# Qwiic-OpenLog.net
KiCad netlist of a schematic drawn in EAGLE
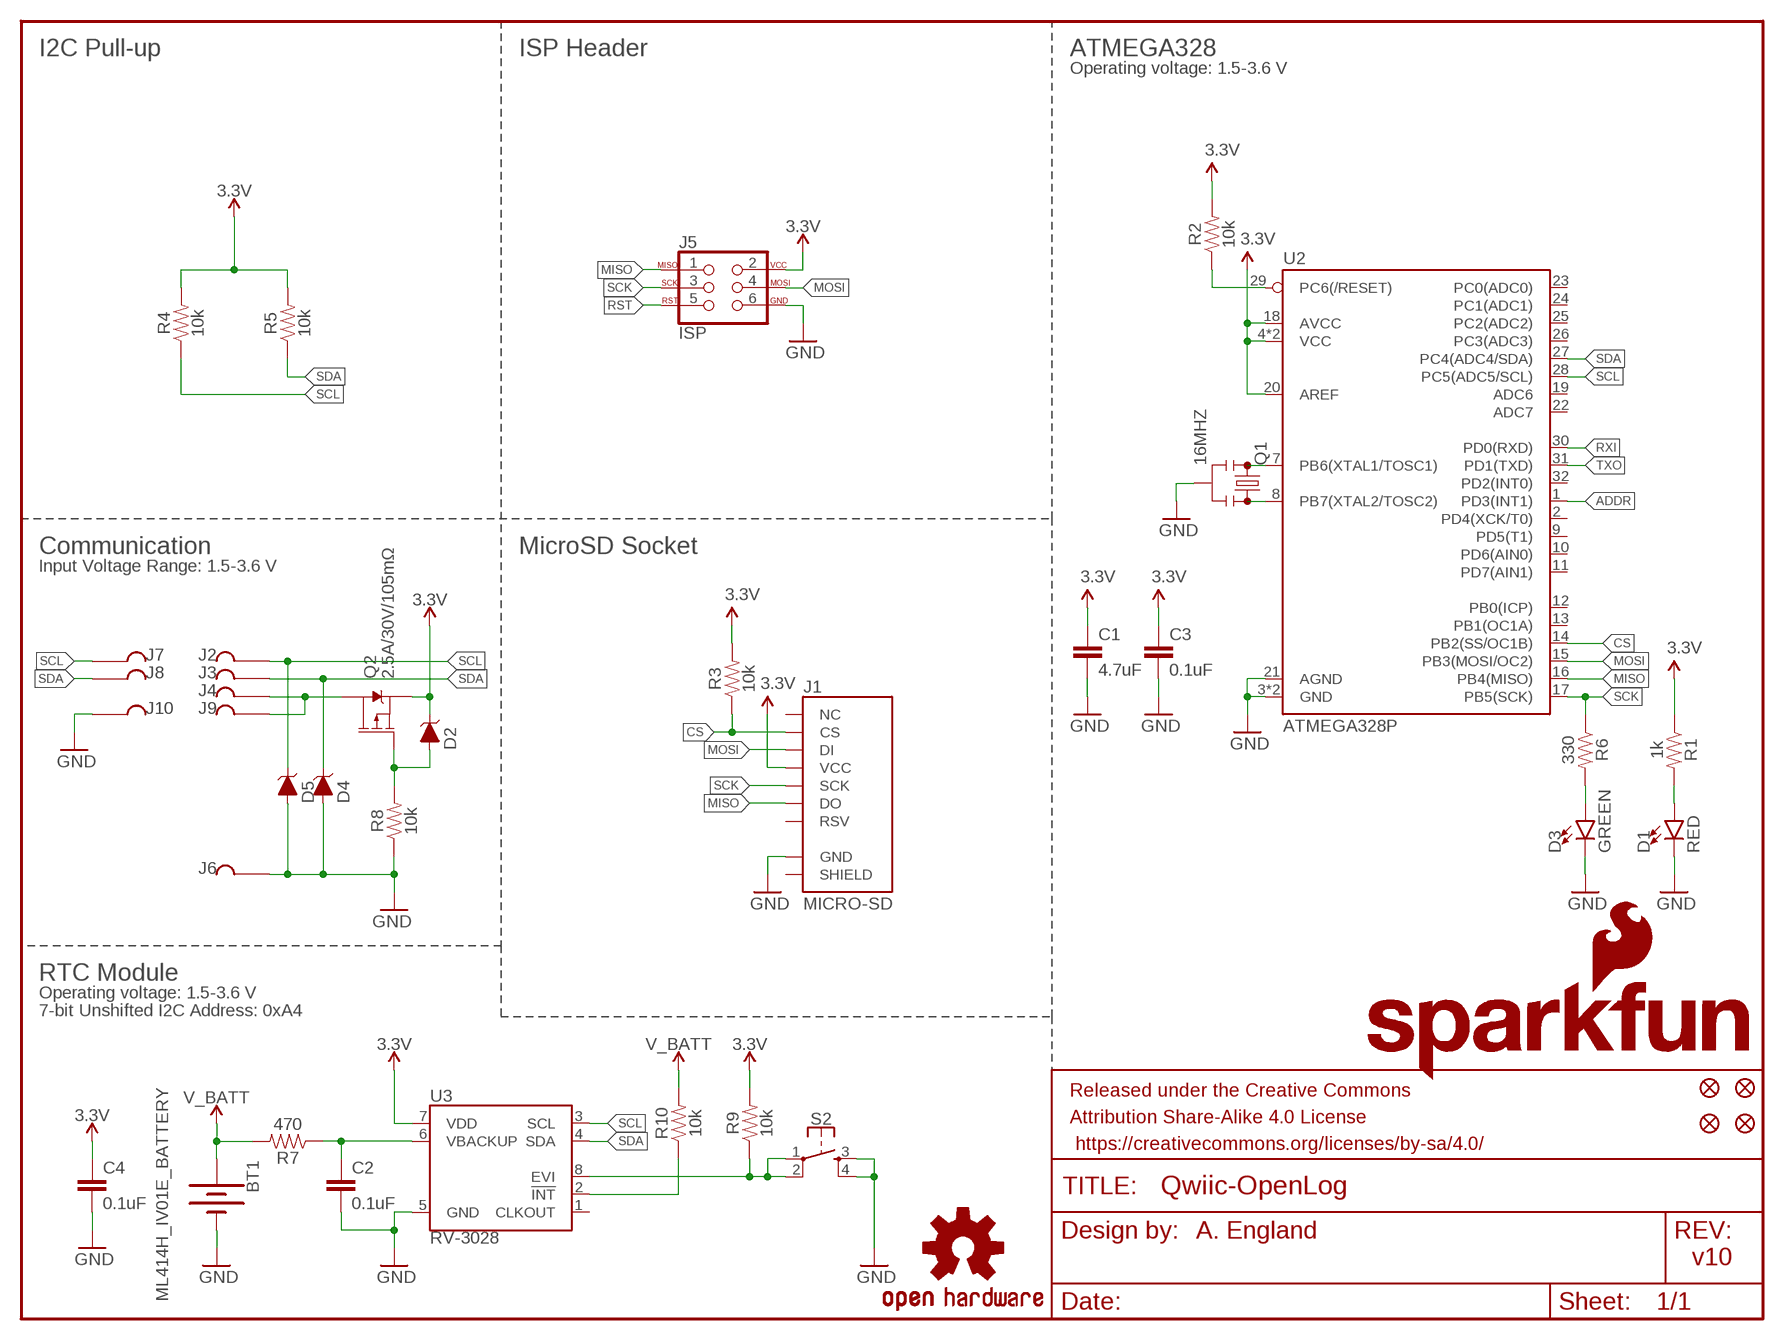
[diagram p0: schematic, sheet 1]

(export (version "E")
  (design (tool "Eeschema 10.0.6"))
  (components
    (comp (ref "BT1")
      (value "ML414H_IV01E_BATTERY")
      (footprint "eagle-import:ML414H_IV01E")
      (libsource (lib "eagle-import") (part "ML414H_IV01E_BATTERY"))
    )
    (comp (ref "C1")
      (value "4.7uF")
      (footprint "eagle-import:0603")
      (libsource (lib "eagle-import") (part "4.7UF-0603-6.3V-(10%)"))
    )
    (comp (ref "C2")
      (value "0.1uF")
      (footprint "eagle-import:0603")
      (libsource (lib "eagle-import") (part "0.1UF-0603-25V-(+80/-20%)"))
    )
    (comp (ref "C3")
      (value "0.1uF")
      (footprint "eagle-import:0603")
      (libsource (lib "eagle-import") (part "0.1UF-0603-25V-(+80/-20%)"))
    )
    (comp (ref "C4")
      (value "0.1uF")
      (footprint "eagle-import:0603")
      (libsource (lib "eagle-import") (part "0.1UF-0603-25V-(+80/-20%)"))
    )
    (comp (ref "D1")
      (value "RED")
      (footprint "eagle-import:LED-0603")
      (libsource (lib "eagle-import") (part "LED-RED0603"))
    )
    (comp (ref "D2")
      (value "3.6V")
      (footprint "eagle-import:SOD-323")
      (libsource (lib "eagle-import") (part "DIODE-ZENER-BZT52C3V6S"))
    )
    (comp (ref "D3")
      (value "GREEN")
      (footprint "eagle-import:LED-0603")
      (libsource (lib "eagle-import") (part "LED-GREEN0603"))
    )
    (comp (ref "D4")
      (value "3.6V")
      (footprint "eagle-import:SOD-323")
      (libsource (lib "eagle-import") (part "DIODE-ZENER-BZT52C3V6S"))
    )
    (comp (ref "D5")
      (value "3.6V")
      (footprint "eagle-import:SOD-323")
      (libsource (lib "eagle-import") (part "DIODE-ZENER-BZT52C3V6S"))
    )
    (comp (ref "FID1")
      (value "FIDUCIALUFIDUCIAL")
      (footprint "eagle-import:FIDUCIAL-MICRO")
      (libsource (lib "eagle-import") (part "FIDUCIALUFIDUCIAL"))
    )
    (comp (ref "FID2")
      (value "FIDUCIALUFIDUCIAL")
      (footprint "eagle-import:FIDUCIAL-MICRO")
      (libsource (lib "eagle-import") (part "FIDUCIALUFIDUCIAL"))
    )
    (comp (ref "FID3")
      (value "FIDUCIALUFIDUCIAL")
      (footprint "eagle-import:FIDUCIAL-MICRO")
      (libsource (lib "eagle-import") (part "FIDUCIALUFIDUCIAL"))
    )
    (comp (ref "FID4")
      (value "FIDUCIALUFIDUCIAL")
      (footprint "eagle-import:FIDUCIAL-MICRO")
      (libsource (lib "eagle-import") (part "FIDUCIALUFIDUCIAL"))
    )
    (comp (ref "FRAME1")
      (value "FRAME-LETTER")
      (footprint "eagle-import:CREATIVE_COMMONS")
      (libsource (lib "eagle-import") (part "FRAME-LETTER"))
    )
    (comp (ref "J1")
      (value "MICRO-SD")
      (footprint "eagle-import:MICRO-SD-SOCKET")
      (libsource (lib "eagle-import") (part "MICRO-SD_CARD_SOCKETPUSH-PUSH"))
    )
    (comp (ref "J2")
      (value "GATORGATOR_MINI")
      (footprint "eagle-import:GATOR_MINI")
      (libsource (lib "eagle-import") (part "GATORGATOR_MINI"))
    )
    (comp (ref "J3")
      (value "GATORGATOR_MINI")
      (footprint "eagle-import:GATOR_MINI")
      (libsource (lib "eagle-import") (part "GATORGATOR_MINI"))
    )
    (comp (ref "J4")
      (value "GATORGATOR_MINI")
      (footprint "eagle-import:GATOR_MINI")
      (libsource (lib "eagle-import") (part "GATORGATOR_MINI"))
    )
    (comp (ref "J5")
      (value "ISP")
      (footprint "eagle-import:2X3_TEST_POINTS")
      (libsource (lib "eagle-import") (part "AVR_SPI_PROG_3X2TESTPOINTS"))
    )
    (comp (ref "J6")
      (value "GATORGATOR_MINI")
      (footprint "eagle-import:GATOR_MINI")
      (libsource (lib "eagle-import") (part "GATORGATOR_MINI"))
    )
    (comp (ref "J7")
      (value "GATORGATOR_MINI")
      (footprint "eagle-import:GATOR_MINI")
      (libsource (lib "eagle-import") (part "GATORGATOR_MINI"))
    )
    (comp (ref "J8")
      (value "GATORGATOR_MINI")
      (footprint "eagle-import:GATOR_MINI")
      (libsource (lib "eagle-import") (part "GATORGATOR_MINI"))
    )
    (comp (ref "J9")
      (value "GATORGATOR_MINI")
      (footprint "eagle-import:GATOR_MINI")
      (libsource (lib "eagle-import") (part "GATORGATOR_MINI"))
    )
    (comp (ref "J10")
      (value "GATORGATOR_MINI")
      (footprint "eagle-import:GATOR_MINI")
      (libsource (lib "eagle-import") (part "GATORGATOR_MINI"))
    )
    (comp (ref "LOGO1")
      (value "SFE_LOGO_FLAME.1_INCH")
      (footprint "eagle-import:SFE_LOGO_FLAME_.1")
      (libsource (lib "eagle-import") (part "SFE_LOGO_FLAME.1_INCH"))
    )
    (comp (ref "LOGO2")
      (value "OSHW-LOGOMINI")
      (footprint "eagle-import:OSHW-LOGO-MINI")
      (libsource (lib "eagle-import") (part "OSHW-LOGOMINI"))
    )
    (comp (ref "LOGO4")
      (value "SFE_LOGO_NAME_FLAME.1_INCH")
      (footprint "eagle-import:SFE_LOGO_NAME_FLAME_.1")
      (libsource (lib "eagle-import") (part "SFE_LOGO_NAME_FLAME.1_INCH"))
    )
    (comp (ref "Q1")
      (value "16MHZ")
      (footprint "eagle-import:RESONATOR-SMD")
      (libsource (lib "eagle-import") (part "RESONATOR16MHZ"))
    )
    (comp (ref "Q2")
      (value "2.5A/30V/105mΩ")
      (footprint "eagle-import:SOT23-3")
      (libsource (lib "eagle-import") (part "MOSFET_PCH-DMG2307L"))
    )
    (comp (ref "R1")
      (value "1k")
      (footprint "eagle-import:0603")
      (libsource (lib "eagle-import") (part "1KOHM-0603-1/10W-1%"))
    )
    (comp (ref "R2")
      (value "10k")
      (footprint "eagle-import:0603")
      (libsource (lib "eagle-import") (part "10KOHM-0603-1/10W-1%"))
    )
    (comp (ref "R3")
      (value "10k")
      (footprint "eagle-import:0603")
      (libsource (lib "eagle-import") (part "10KOHM-0603-1/10W-1%"))
    )
    (comp (ref "R4")
      (value "10k")
      (footprint "eagle-import:0603")
      (libsource (lib "eagle-import") (part "10KOHM-0603-1/10W-1%"))
    )
    (comp (ref "R5")
      (value "10k")
      (footprint "eagle-import:0603")
      (libsource (lib "eagle-import") (part "10KOHM-0603-1/10W-1%"))
    )
    (comp (ref "R6")
      (value "330")
      (footprint "eagle-import:0603")
      (libsource (lib "eagle-import") (part "330OHM-0603-1/10W-1%"))
    )
    (comp (ref "R7")
      (value "470")
      (footprint "eagle-import:0603")
      (libsource (lib "eagle-import") (part "470OHM-0603-1/10W-1%"))
    )
    (comp (ref "R8")
      (value "10k")
      (footprint "eagle-import:0603")
      (libsource (lib "eagle-import") (part "10KOHM-0603-1/10W-1%"))
    )
    (comp (ref "R9")
      (value "10k")
      (footprint "eagle-import:0603")
      (libsource (lib "eagle-import") (part "10KOHM-0603-1/10W-1%"))
    )
    (comp (ref "R10")
      (value "10k")
      (footprint "eagle-import:0603")
      (libsource (lib "eagle-import") (part "10KOHM-0603-1/10W-1%"))
    )
    (comp (ref "S2")
      (value "MOMENTARY-SWITCH-SPST-2-SMD-5.2MM-TALL")
      (footprint "eagle-import:TACTILE_SWITCH_SMD_5.2MM")
      (libsource (lib "eagle-import") (part "MOMENTARY-SWITCH-SPST-2-SMD-5.2MM-TALL"))
    )
    (comp (ref "U2")
      (value "ATMEGA328P")
      (footprint "eagle-import:TQFP32-08")
      (libsource (lib "eagle-import") (part "ATMEGA328P_TQFP"))
    )
    (comp (ref "U3")
      (value "RV-3028")
      (footprint "eagle-import:RV-3028")
      (libsource (lib "eagle-import") (part "RV-3028"))
    )
  )
  (nets
    (net (code "1") (name "3.3V") (class "Default")
      (node (ref "C1") (pin "1") (pinfunction "1_1") (pintype "passive"))
      (node (ref "C3") (pin "1") (pinfunction "1_1") (pintype "passive"))
      (node (ref "C4") (pin "1") (pinfunction "1_1") (pintype "passive"))
      (node (ref "D2") (pin "C") (pinfunction "C_C") (pintype "passive"))
      (node (ref "J1") (pin "VCC") (pinfunction "VCC_VCC") (pintype "bidirectional"))
      (node (ref "J5") (pin "2") (pinfunction "2_2") (pintype "passive"))
      (node (ref "Q2") (pin "2") (pinfunction "S_2") (pintype "bidirectional"))
      (node (ref "R1") (pin "1") (pinfunction "1_1") (pintype "passive"))
      (node (ref "R2") (pin "2") (pinfunction "2_2") (pintype "passive"))
      (node (ref "R3") (pin "2") (pinfunction "2_2") (pintype "passive"))
      (node (ref "R4") (pin "2") (pinfunction "2_2") (pintype "passive"))
      (node (ref "R5") (pin "2") (pinfunction "2_2") (pintype "passive"))
      (node (ref "R9") (pin "2") (pinfunction "2_2") (pintype "passive"))
      (node (ref "U2") (pin "18") (pinfunction "AVCC_18") (pintype "bidirectional"))
      (node (ref "U2") (pin "20") (pinfunction "AREF_20") (pintype "bidirectional"))
      (node (ref "U2") (pin "4") (pinfunction "VCC_4") (pintype "bidirectional"))
      (node (ref "U2") (pin "6") (pinfunction "VCC_6") (pintype "bidirectional"))
      (node (ref "U3") (pin "7") (pinfunction "VDD_7") (pintype "bidirectional"))
    )
    (net (code "2") (name "ADDR") (class "Default")
      (node (ref "U2") (pin "1") (pinfunction "PD3(INT1)_1") (pintype "bidirectional"))
    )
    (net (code "3") (name "CS") (class "Default")
      (node (ref "J1") (pin "CS") (pinfunction "CS_CS") (pintype "bidirectional"))
      (node (ref "R3") (pin "1") (pinfunction "1_1") (pintype "passive"))
      (node (ref "U2") (pin "14") (pinfunction "PB2(SS/OC1B)_14") (pintype "bidirectional"))
    )
    (net (code "4") (name "GND") (class "Default")
      (node (ref "BT1") (pin "-") (pinfunction "-_-") (pintype "power_in"))
      (node (ref "C1") (pin "2") (pinfunction "2_2") (pintype "passive"))
      (node (ref "C2") (pin "2") (pinfunction "2_2") (pintype "passive"))
      (node (ref "C3") (pin "2") (pinfunction "2_2") (pintype "passive"))
      (node (ref "C4") (pin "2") (pinfunction "2_2") (pintype "passive"))
      (node (ref "D1") (pin "C") (pinfunction "C_C") (pintype "passive"))
      (node (ref "D3") (pin "C") (pinfunction "C_C") (pintype "passive"))
      (node (ref "D4") (pin "A") (pinfunction "A_A") (pintype "passive"))
      (node (ref "D5") (pin "A") (pinfunction "A_A") (pintype "passive"))
      (node (ref "J1") (pin "GND") (pinfunction "GND_GND") (pintype "bidirectional"))
      (node (ref "J10") (pin "P$2") (pinfunction "P$1_P$2") (pintype "bidirectional"))
      (node (ref "J5") (pin "6") (pinfunction "6_6") (pintype "passive"))
      (node (ref "J6") (pin "P$2") (pinfunction "P$1_P$2") (pintype "bidirectional"))
      (node (ref "Q1") (pin "2") (pinfunction "2_2") (pintype "passive"))
      (node (ref "R8") (pin "1") (pinfunction "1_1") (pintype "passive"))
      (node (ref "S2") (pin "3") (pinfunction "3_3") (pintype "passive"))
      (node (ref "S2") (pin "4") (pinfunction "4_4") (pintype "passive"))
      (node (ref "U2") (pin "21") (pinfunction "AGND_21") (pintype "bidirectional"))
      (node (ref "U2") (pin "3") (pinfunction "GND_3") (pintype "bidirectional"))
      (node (ref "U2") (pin "5") (pinfunction "GND_5") (pintype "bidirectional"))
      (node (ref "U3") (pin "5") (pinfunction "GND_5") (pintype "bidirectional"))
    )
    (net (code "5") (name "MISO") (class "Default")
      (node (ref "J1") (pin "DO") (pinfunction "DO_DO") (pintype "bidirectional"))
      (node (ref "J5") (pin "1") (pinfunction "1_1") (pintype "passive"))
      (node (ref "U2") (pin "16") (pinfunction "PB4(MISO)_16") (pintype "bidirectional"))
    )
    (net (code "6") (name "MOSI") (class "Default")
      (node (ref "J1") (pin "DI") (pinfunction "DI_DI") (pintype "bidirectional"))
      (node (ref "J5") (pin "4") (pinfunction "4_4") (pintype "passive"))
      (node (ref "U2") (pin "15") (pinfunction "PB3(MOSI/OC2)_15") (pintype "bidirectional"))
    )
    (net (code "7") (name "Net-(D1-PadA)") (class "Default")
      (node (ref "D1") (pin "A") (pinfunction "A_A") (pintype "passive"))
      (node (ref "R1") (pin "2") (pinfunction "2_2") (pintype "passive"))
    )
    (net (code "8") (name "Net-(D3-PadA)") (class "Default")
      (node (ref "D3") (pin "A") (pinfunction "A_A") (pintype "passive"))
      (node (ref "R6") (pin "2") (pinfunction "2_2") (pintype "passive"))
    )
    (net (code "9") (name "Net-(J4-P$1)") (class "Default")
      (node (ref "J4") (pin "P$2") (pinfunction "P$1_P$2") (pintype "bidirectional"))
      (node (ref "J9") (pin "P$2") (pinfunction "P$1_P$2") (pintype "bidirectional"))
      (node (ref "Q2") (pin "3") (pinfunction "D_3") (pintype "bidirectional"))
    )
    (net (code "10") (name "Net-(Q2-G)") (class "Default")
      (node (ref "D2") (pin "A") (pinfunction "A_A") (pintype "passive"))
      (node (ref "Q2") (pin "1") (pinfunction "G_1") (pintype "bidirectional"))
      (node (ref "R8") (pin "2") (pinfunction "2_2") (pintype "passive"))
    )
    (net (code "11") (name "Net-(U2-PB6(XTAL1{slash}TOSC1))") (class "Default")
      (node (ref "Q1") (pin "3") (pinfunction "3_3") (pintype "passive"))
      (node (ref "U2") (pin "7") (pinfunction "PB6(XTAL1/TOSC1)_7") (pintype "bidirectional"))
    )
    (net (code "12") (name "Net-(U2-PB7(XTAL2{slash}TOSC2))") (class "Default")
      (node (ref "Q1") (pin "1") (pinfunction "1_1") (pintype "passive"))
      (node (ref "U2") (pin "8") (pinfunction "PB7(XTAL2/TOSC2)_8") (pintype "bidirectional"))
    )
    (net (code "13") (name "Net-(U3-EVI)") (class "Default")
      (node (ref "R9") (pin "1") (pinfunction "1_1") (pintype "passive"))
      (node (ref "S2") (pin "1") (pinfunction "1_1") (pintype "passive"))
      (node (ref "S2") (pin "2") (pinfunction "2_2") (pintype "passive"))
      (node (ref "U3") (pin "8") (pinfunction "EVI_8") (pintype "bidirectional"))
    )
    (net (code "14") (name "Net-(U3-VBACKUP)") (class "Default")
      (node (ref "C2") (pin "1") (pinfunction "1_1") (pintype "passive"))
      (node (ref "R7") (pin "1") (pinfunction "1_1") (pintype "passive"))
      (node (ref "U3") (pin "6") (pinfunction "VBACKUP_6") (pintype "bidirectional"))
    )
    (net (code "15") (name "Net-(U3-~{INT})") (class "Default")
      (node (ref "R10") (pin "1") (pinfunction "1_1") (pintype "passive"))
      (node (ref "U3") (pin "2") (pinfunction "~{INT}_2") (pintype "bidirectional"))
    )
    (net (code "16") (name "RST") (class "Default")
      (node (ref "J5") (pin "5") (pinfunction "5_5") (pintype "passive"))
      (node (ref "R2") (pin "1") (pinfunction "1_1") (pintype "passive"))
      (node (ref "U2") (pin "29") (pinfunction "PC6(/RESET)_29") (pintype "bidirectional"))
    )
    (net (code "17") (name "RXI") (class "Default")
      (node (ref "U2") (pin "30") (pinfunction "PD0(RXD)_30") (pintype "bidirectional"))
    )
    (net (code "18") (name "SCK") (class "Default")
      (node (ref "J1") (pin "SCLK") (pinfunction "SCK_SCLK") (pintype "bidirectional"))
      (node (ref "J5") (pin "3") (pinfunction "3_3") (pintype "passive"))
      (node (ref "R6") (pin "1") (pinfunction "1_1") (pintype "passive"))
      (node (ref "U2") (pin "17") (pinfunction "PB5(SCK)_17") (pintype "bidirectional"))
    )
    (net (code "19") (name "SCL") (class "Default")
      (node (ref "D5") (pin "C") (pinfunction "C_C") (pintype "passive"))
      (node (ref "J2") (pin "P$2") (pinfunction "P$1_P$2") (pintype "bidirectional"))
      (node (ref "J7") (pin "P$2") (pinfunction "P$1_P$2") (pintype "bidirectional"))
      (node (ref "R4") (pin "1") (pinfunction "1_1") (pintype "passive"))
      (node (ref "U2") (pin "28") (pinfunction "PC5(ADC5/SCL)_28") (pintype "bidirectional"))
      (node (ref "U3") (pin "3") (pinfunction "SCL_3") (pintype "bidirectional"))
    )
    (net (code "20") (name "SDA") (class "Default")
      (node (ref "D4") (pin "C") (pinfunction "C_C") (pintype "passive"))
      (node (ref "J3") (pin "P$2") (pinfunction "P$1_P$2") (pintype "bidirectional"))
      (node (ref "J8") (pin "P$2") (pinfunction "P$1_P$2") (pintype "bidirectional"))
      (node (ref "R5") (pin "1") (pinfunction "1_1") (pintype "passive"))
      (node (ref "U2") (pin "27") (pinfunction "PC4(ADC4/SDA)_27") (pintype "bidirectional"))
      (node (ref "U3") (pin "4") (pinfunction "SDA_4") (pintype "bidirectional"))
    )
    (net (code "21") (name "TXO") (class "Default")
      (node (ref "U2") (pin "31") (pinfunction "PD1(TXD)_31") (pintype "bidirectional"))
    )
    (net (code "22") (name "V_BATT") (class "Default")
      (node (ref "BT1") (pin "+") (pinfunction "+_+") (pintype "power_in"))
      (node (ref "R10") (pin "2") (pinfunction "2_2") (pintype "passive"))
      (node (ref "R7") (pin "2") (pinfunction "2_2") (pintype "passive"))
    )
    (net (code "23") (name "unconnected-(J1-NC-PadRSV2)") (class "Default")
      (node (ref "J1") (pin "RSV2") (pinfunction "NC_RSV2") (pintype "bidirectional"))
    )
    (net (code "24") (name "unconnected-(J1-RSV-PadRSV1)") (class "Default")
      (node (ref "J1") (pin "RSV1") (pinfunction "RSV_RSV1") (pintype "bidirectional"))
    )
    (net (code "25") (name "unconnected-(J1-SHIELD-PadCD1)") (class "Default")
      (node (ref "J1") (pin "CD1") (pinfunction "SHIELD_CD1") (pintype "bidirectional"))
    )
    (net (code "26") (name "unconnected-(U2-ADC6-Pad19)") (class "Default")
      (node (ref "U2") (pin "19") (pinfunction "ADC6_19") (pintype "bidirectional"))
    )
    (net (code "27") (name "unconnected-(U2-ADC7-Pad22)") (class "Default")
      (node (ref "U2") (pin "22") (pinfunction "ADC7_22") (pintype "bidirectional"))
    )
    (net (code "28") (name "unconnected-(U2-PB0(ICP)-Pad12)") (class "Default")
      (node (ref "U2") (pin "12") (pinfunction "PB0(ICP)_12") (pintype "bidirectional"))
    )
    (net (code "29") (name "unconnected-(U2-PB1(OC1A)-Pad13)") (class "Default")
      (node (ref "U2") (pin "13") (pinfunction "PB1(OC1A)_13") (pintype "bidirectional"))
    )
    (net (code "30") (name "unconnected-(U2-PC0(ADC0)-Pad23)") (class "Default")
      (node (ref "U2") (pin "23") (pinfunction "PC0(ADC0)_23") (pintype "bidirectional"))
    )
    (net (code "31") (name "unconnected-(U2-PC1(ADC1)-Pad24)") (class "Default")
      (node (ref "U2") (pin "24") (pinfunction "PC1(ADC1)_24") (pintype "bidirectional"))
    )
    (net (code "32") (name "unconnected-(U2-PC2(ADC2)-Pad25)") (class "Default")
      (node (ref "U2") (pin "25") (pinfunction "PC2(ADC2)_25") (pintype "bidirectional"))
    )
    (net (code "33") (name "unconnected-(U2-PC3(ADC3)-Pad26)") (class "Default")
      (node (ref "U2") (pin "26") (pinfunction "PC3(ADC3)_26") (pintype "bidirectional"))
    )
    (net (code "34") (name "unconnected-(U2-PD2(INT0)-Pad32)") (class "Default")
      (node (ref "U2") (pin "32") (pinfunction "PD2(INT0)_32") (pintype "bidirectional"))
    )
    (net (code "35") (name "unconnected-(U2-PD4(XCK{slash}T0)-Pad2)") (class "Default")
      (node (ref "U2") (pin "2") (pinfunction "PD4(XCK/T0)_2") (pintype "bidirectional"))
    )
    (net (code "36") (name "unconnected-(U2-PD5(T1)-Pad9)") (class "Default")
      (node (ref "U2") (pin "9") (pinfunction "PD5(T1)_9") (pintype "bidirectional"))
    )
    (net (code "37") (name "unconnected-(U2-PD6(AIN0)-Pad10)") (class "Default")
      (node (ref "U2") (pin "10") (pinfunction "PD6(AIN0)_10") (pintype "bidirectional"))
    )
    (net (code "38") (name "unconnected-(U2-PD7(AIN1)-Pad11)") (class "Default")
      (node (ref "U2") (pin "11") (pinfunction "PD7(AIN1)_11") (pintype "bidirectional"))
    )
    (net (code "39") (name "unconnected-(U3-CLKOUT-Pad1)") (class "Default")
      (node (ref "U3") (pin "1") (pinfunction "CLKOUT_1") (pintype "bidirectional"))
    )
  )
)
